# led-ring.net
KiCad netlist of a schematic drawn in EAGLE
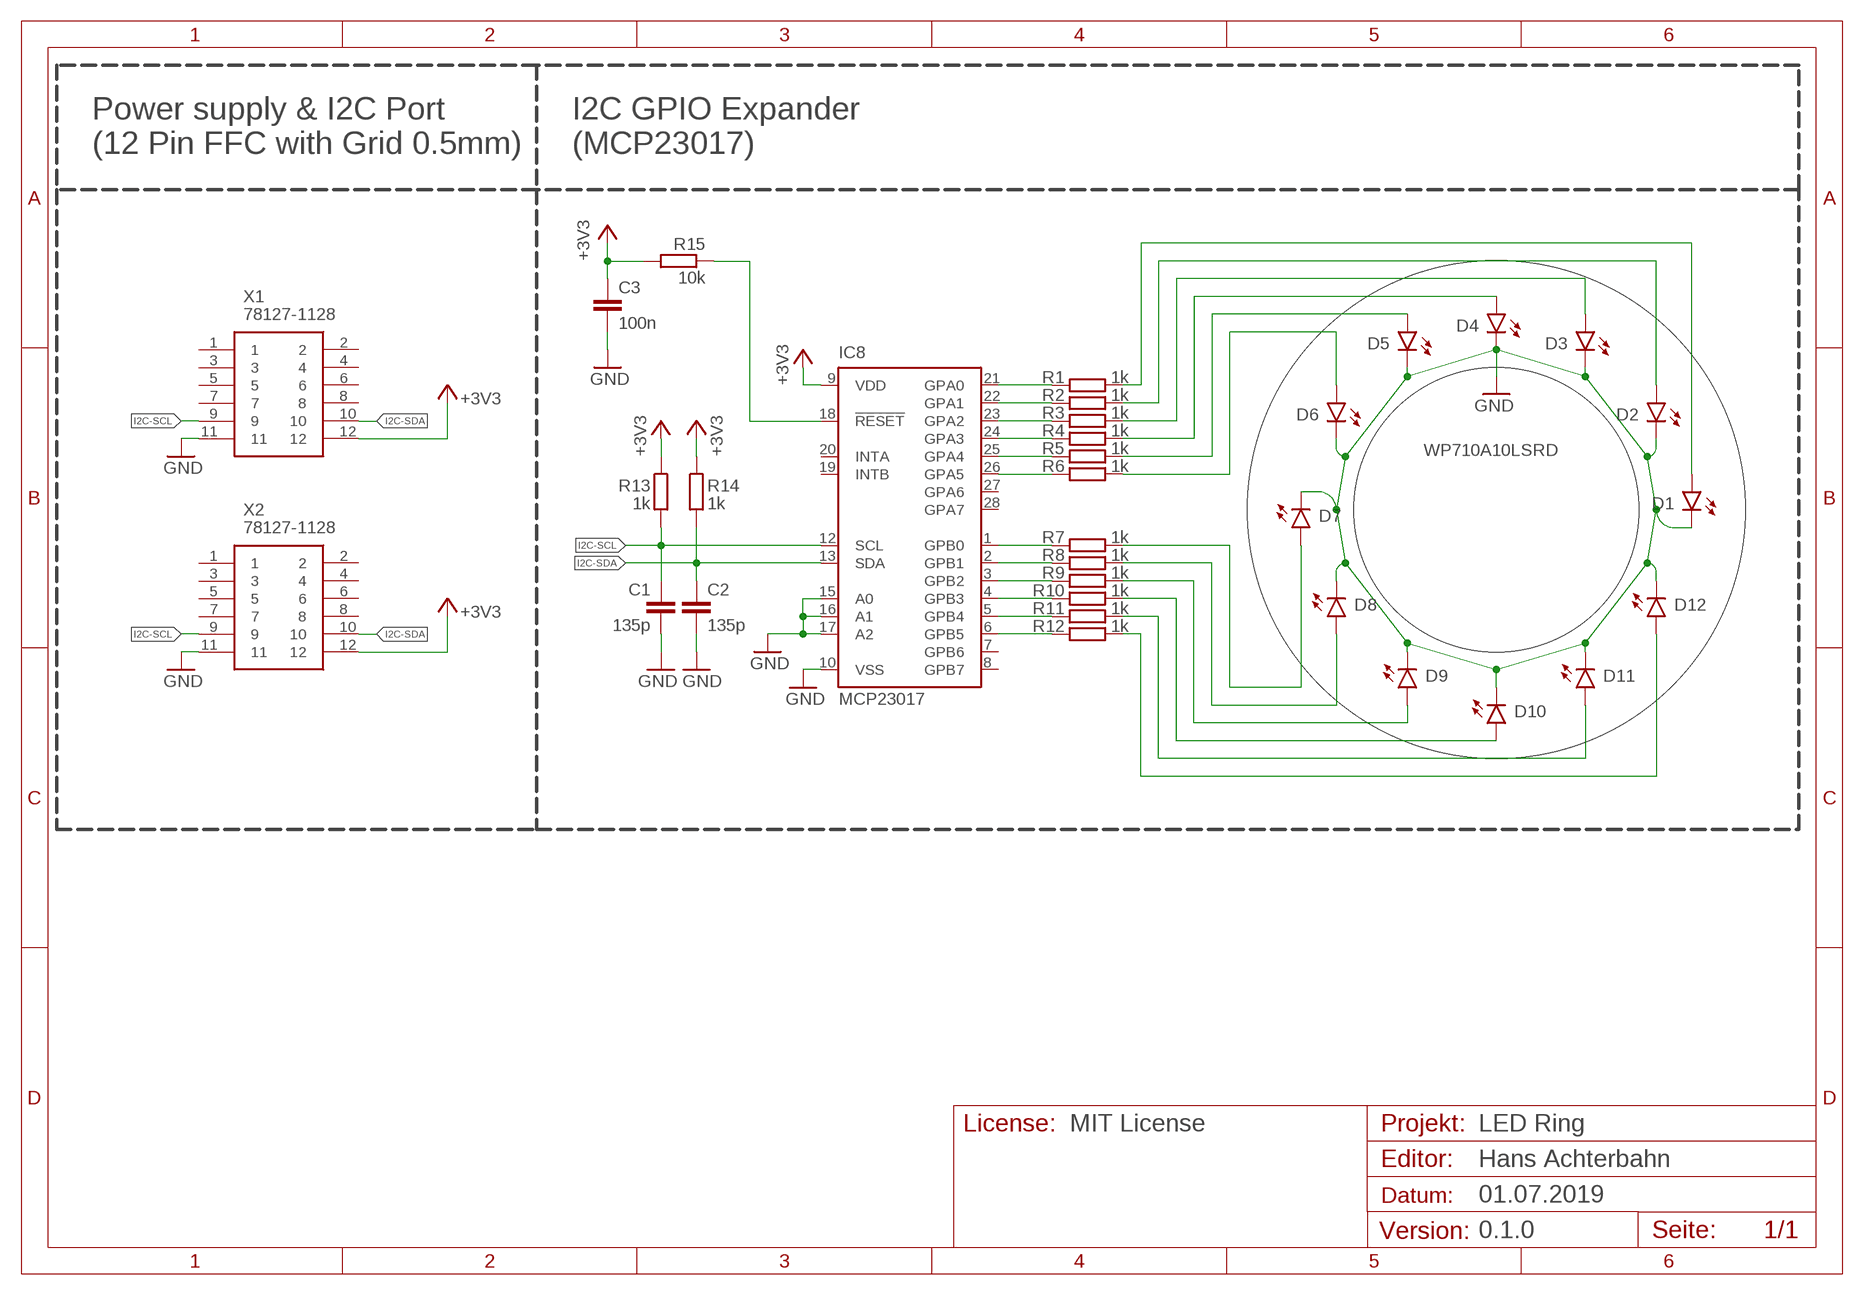
[diagram p0: schematic, sheet 1]

(export (version "E")
  (design (tool "Eeschema 10.0.6"))
  (components
    (comp (ref "C1")
      (value "135p")
      (footprint "eagle-import:C0603")
      (libsource (lib "eagle-import") (part "C-EUC0603"))
    )
    (comp (ref "C2")
      (value "135p")
      (footprint "eagle-import:C0603")
      (libsource (lib "eagle-import") (part "C-EUC0603"))
    )
    (comp (ref "C3")
      (value "100n")
      (footprint "eagle-import:C0603")
      (fields
        (field (name "MF") "AVX")
        (field (name "MFN") "0603YC104JAT2A")
        (field (name "MOUSER") "581-0603YC104J")
        (field (name "RS-ONLINE") "391-246 ")
      )
      (libsource (lib "eagle-import") (part "C-EUC0603"))
    )
    (comp (ref "D1")
      (value "WP710A10LSRD")
      (footprint "eagle-import:RADIAL_3MM")
      (fields
        (field (name "DIGIKEY_PART_NUMBER") "160-1708-ND")
        (field (name "MANUFACTURER") "Lite-On Inc.")
        (field (name "MPN") "LTL-1CHE")
        (field (name "CREATED_BY") "PCBLayout.com")
      )
      (libsource (lib "eagle-import") (part "LTL-1CHE"))
    )
    (comp (ref "D2")
      (value "WP710A10LSRD")
      (footprint "eagle-import:RADIAL_3MM")
      (fields
        (field (name "DIGIKEY_PART_NUMBER") "160-1708-ND")
        (field (name "MANUFACTURER") "Lite-On Inc.")
        (field (name "MPN") "LTL-1CHE")
        (field (name "CREATED_BY") "PCBLayout.com")
      )
      (libsource (lib "eagle-import") (part "LTL-1CHE"))
    )
    (comp (ref "D3")
      (value "WP710A10LSRD")
      (footprint "eagle-import:RADIAL_3MM")
      (fields
        (field (name "DIGIKEY_PART_NUMBER") "160-1708-ND")
        (field (name "MANUFACTURER") "Lite-On Inc.")
        (field (name "MPN") "LTL-1CHE")
        (field (name "CREATED_BY") "PCBLayout.com")
      )
      (libsource (lib "eagle-import") (part "LTL-1CHE"))
    )
    (comp (ref "D4")
      (value "WP710A10LSRD")
      (footprint "eagle-import:RADIAL_3MM")
      (fields
        (field (name "DIGIKEY_PART_NUMBER") "160-1708-ND")
        (field (name "MANUFACTURER") "Lite-On Inc.")
        (field (name "MPN") "LTL-1CHE")
        (field (name "CREATED_BY") "PCBLayout.com")
      )
      (libsource (lib "eagle-import") (part "LTL-1CHE"))
    )
    (comp (ref "D5")
      (value "WP710A10LSRD")
      (footprint "eagle-import:RADIAL_3MM")
      (fields
        (field (name "DIGIKEY_PART_NUMBER") "160-1708-ND")
        (field (name "MANUFACTURER") "Lite-On Inc.")
        (field (name "MPN") "LTL-1CHE")
        (field (name "CREATED_BY") "PCBLayout.com")
      )
      (libsource (lib "eagle-import") (part "LTL-1CHE"))
    )
    (comp (ref "D6")
      (value "WP710A10LSRD")
      (footprint "eagle-import:RADIAL_3MM")
      (fields
        (field (name "DIGIKEY_PART_NUMBER") "160-1708-ND")
        (field (name "MANUFACTURER") "Lite-On Inc.")
        (field (name "MPN") "LTL-1CHE")
        (field (name "CREATED_BY") "PCBLayout.com")
      )
      (libsource (lib "eagle-import") (part "LTL-1CHE"))
    )
    (comp (ref "D7")
      (value "WP710A10LSRD")
      (footprint "eagle-import:RADIAL_3MM")
      (fields
        (field (name "DIGIKEY_PART_NUMBER") "160-1708-ND")
        (field (name "MANUFACTURER") "Lite-On Inc.")
        (field (name "MPN") "LTL-1CHE")
        (field (name "CREATED_BY") "PCBLayout.com")
      )
      (libsource (lib "eagle-import") (part "LTL-1CHE"))
    )
    (comp (ref "D8")
      (value "WP710A10LSRD")
      (footprint "eagle-import:RADIAL_3MM")
      (fields
        (field (name "DIGIKEY_PART_NUMBER") "160-1708-ND")
        (field (name "MANUFACTURER") "Lite-On Inc.")
        (field (name "MPN") "LTL-1CHE")
        (field (name "CREATED_BY") "PCBLayout.com")
      )
      (libsource (lib "eagle-import") (part "LTL-1CHE"))
    )
    (comp (ref "D9")
      (value "WP710A10LSRD")
      (footprint "eagle-import:RADIAL_3MM")
      (fields
        (field (name "DIGIKEY_PART_NUMBER") "160-1708-ND")
        (field (name "MANUFACTURER") "Lite-On Inc.")
        (field (name "MPN") "LTL-1CHE")
        (field (name "CREATED_BY") "PCBLayout.com")
      )
      (libsource (lib "eagle-import") (part "LTL-1CHE"))
    )
    (comp (ref "D10")
      (value "WP710A10LSRD")
      (footprint "eagle-import:RADIAL_3MM")
      (fields
        (field (name "DIGIKEY_PART_NUMBER") "160-1708-ND")
        (field (name "MANUFACTURER") "Lite-On Inc.")
        (field (name "MPN") "LTL-1CHE")
        (field (name "CREATED_BY") "PCBLayout.com")
      )
      (libsource (lib "eagle-import") (part "LTL-1CHE"))
    )
    (comp (ref "D11")
      (value "WP710A10LSRD")
      (footprint "eagle-import:RADIAL_3MM")
      (fields
        (field (name "DIGIKEY_PART_NUMBER") "160-1708-ND")
        (field (name "MANUFACTURER") "Lite-On Inc.")
        (field (name "MPN") "LTL-1CHE")
        (field (name "CREATED_BY") "PCBLayout.com")
      )
      (libsource (lib "eagle-import") (part "LTL-1CHE"))
    )
    (comp (ref "D12")
      (value "WP710A10LSRD")
      (footprint "eagle-import:RADIAL_3MM")
      (fields
        (field (name "DIGIKEY_PART_NUMBER") "160-1708-ND")
        (field (name "MANUFACTURER") "Lite-On Inc.")
        (field (name "MPN") "LTL-1CHE")
        (field (name "CREATED_BY") "PCBLayout.com")
      )
      (libsource (lib "eagle-import") (part "LTL-1CHE"))
    )
    (comp (ref "IC8")
      (value "MCP23017")
      (footprint "eagle-import:SOP65P780X200-28")
      (fields (field (name "MF") "Microchip"))
      (libsource (lib "eagle-import") (part "MCP23017"))
    )
    (comp (ref "R1")
      (value "1k")
      (footprint "eagle-import:R0603")
      (libsource (lib "eagle-import") (part "R-EU_R0603"))
    )
    (comp (ref "R2")
      (value "1k")
      (footprint "eagle-import:R0603")
      (libsource (lib "eagle-import") (part "R-EU_R0603"))
    )
    (comp (ref "R3")
      (value "1k")
      (footprint "eagle-import:R0603")
      (libsource (lib "eagle-import") (part "R-EU_R0603"))
    )
    (comp (ref "R4")
      (value "1k")
      (footprint "eagle-import:R0603")
      (libsource (lib "eagle-import") (part "R-EU_R0603"))
    )
    (comp (ref "R5")
      (value "1k")
      (footprint "eagle-import:R0603")
      (libsource (lib "eagle-import") (part "R-EU_R0603"))
    )
    (comp (ref "R6")
      (value "1k")
      (footprint "eagle-import:R0603")
      (libsource (lib "eagle-import") (part "R-EU_R0603"))
    )
    (comp (ref "R7")
      (value "1k")
      (footprint "eagle-import:R0603")
      (libsource (lib "eagle-import") (part "R-EU_R0603"))
    )
    (comp (ref "R8")
      (value "1k")
      (footprint "eagle-import:R0603")
      (libsource (lib "eagle-import") (part "R-EU_R0603"))
    )
    (comp (ref "R9")
      (value "1k")
      (footprint "eagle-import:R0603")
      (libsource (lib "eagle-import") (part "R-EU_R0603"))
    )
    (comp (ref "R10")
      (value "1k")
      (footprint "eagle-import:R0603")
      (libsource (lib "eagle-import") (part "R-EU_R0603"))
    )
    (comp (ref "R11")
      (value "1k")
      (footprint "eagle-import:R0603")
      (libsource (lib "eagle-import") (part "R-EU_R0603"))
    )
    (comp (ref "R12")
      (value "1k")
      (footprint "eagle-import:R0603")
      (libsource (lib "eagle-import") (part "R-EU_R0603"))
    )
    (comp (ref "R13")
      (value "1k")
      (footprint "eagle-import:R0603")
      (libsource (lib "eagle-import") (part "R-EU_R0603"))
    )
    (comp (ref "R14")
      (value "1k")
      (footprint "eagle-import:R0603")
      (libsource (lib "eagle-import") (part "R-EU_R0603"))
    )
    (comp (ref "R15")
      (value "10k")
      (footprint "eagle-import:R0603")
      (fields (field (name "MF") "Vishay") (field (name "MFN") "CRCW060310K0FKEA"))
      (libsource (lib "eagle-import") (part "R-EU_R0603"))
    )
    (comp (ref "X1")
      (value "78127-1128")
      (footprint "eagle-import:781271128")
      (fields (field (name "MOUSER_PART_NUMBER") "538-78127-1128"))
      (libsource (lib "eagle-import") (part "78127-1128"))
    )
    (comp (ref "X2")
      (value "78127-1128")
      (footprint "eagle-import:781271128")
      (fields (field (name "MOUSER_PART_NUMBER") "538-78127-1128"))
      (libsource (lib "eagle-import") (part "78127-1128"))
    )
  )
  (nets
    (net (code "1") (name "+3V3") (class "Default")
      (node (ref "C3") (pin "1") (pinfunction "1_1") (pintype "passive"))
      (node (ref "IC8") (pin "9") (pinfunction "VDD_9") (pintype "power_in"))
      (node (ref "R13") (pin "1") (pinfunction "1_1") (pintype "passive"))
      (node (ref "R14") (pin "1") (pinfunction "1_1") (pintype "passive"))
      (node (ref "R15") (pin "2") (pinfunction "2_2") (pintype "passive"))
      (node (ref "X1") (pin "12") (pinfunction "12_12") (pintype "bidirectional"))
      (node (ref "X2") (pin "12") (pinfunction "12_12") (pintype "bidirectional"))
    )
    (net (code "2") (name "GND") (class "Default")
      (node (ref "C1") (pin "2") (pinfunction "2_2") (pintype "passive"))
      (node (ref "C2") (pin "2") (pinfunction "2_2") (pintype "passive"))
      (node (ref "C3") (pin "2") (pinfunction "2_2") (pintype "passive"))
      (node (ref "D1") (pin "C") (pinfunction "C_C") (pintype "passive"))
      (node (ref "D10") (pin "C") (pinfunction "C_C") (pintype "passive"))
      (node (ref "D11") (pin "C") (pinfunction "C_C") (pintype "passive"))
      (node (ref "D12") (pin "C") (pinfunction "C_C") (pintype "passive"))
      (node (ref "D2") (pin "C") (pinfunction "C_C") (pintype "passive"))
      (node (ref "D3") (pin "C") (pinfunction "C_C") (pintype "passive"))
      (node (ref "D4") (pin "C") (pinfunction "C_C") (pintype "passive"))
      (node (ref "D5") (pin "C") (pinfunction "C_C") (pintype "passive"))
      (node (ref "D6") (pin "C") (pinfunction "C_C") (pintype "passive"))
      (node (ref "D7") (pin "C") (pinfunction "C_C") (pintype "passive"))
      (node (ref "D8") (pin "C") (pinfunction "C_C") (pintype "passive"))
      (node (ref "D9") (pin "C") (pinfunction "C_C") (pintype "passive"))
      (node (ref "IC8") (pin "10") (pinfunction "VSS_10") (pintype "power_in"))
      (node (ref "IC8") (pin "15") (pinfunction "A0_15") (pintype "input"))
      (node (ref "IC8") (pin "16") (pinfunction "A1_16") (pintype "input"))
      (node (ref "IC8") (pin "17") (pinfunction "A2_17") (pintype "input"))
      (node (ref "X1") (pin "11") (pinfunction "11_11") (pintype "bidirectional"))
      (node (ref "X2") (pin "11") (pinfunction "11_11") (pintype "bidirectional"))
    )
    (net (code "3") (name "I2C-SCL") (class "Default")
      (node (ref "C1") (pin "1") (pinfunction "1_1") (pintype "passive"))
      (node (ref "IC8") (pin "12") (pinfunction "SCL_12") (pintype "input"))
      (node (ref "R13") (pin "2") (pinfunction "2_2") (pintype "passive"))
      (node (ref "X1") (pin "9") (pinfunction "9_9") (pintype "bidirectional"))
      (node (ref "X2") (pin "9") (pinfunction "9_9") (pintype "bidirectional"))
    )
    (net (code "4") (name "I2C-SDA") (class "Default")
      (node (ref "C2") (pin "1") (pinfunction "1_1") (pintype "passive"))
      (node (ref "IC8") (pin "13") (pinfunction "SDA_13") (pintype "bidirectional"))
      (node (ref "R14") (pin "2") (pinfunction "2_2") (pintype "passive"))
      (node (ref "X1") (pin "10") (pinfunction "10_10") (pintype "bidirectional"))
      (node (ref "X2") (pin "10") (pinfunction "10_10") (pintype "bidirectional"))
    )
    (net (code "5") (name "Net-(D1-PadA)") (class "Default")
      (node (ref "D1") (pin "A") (pinfunction "A_A") (pintype "passive"))
      (node (ref "R1") (pin "1") (pinfunction "1_1") (pintype "passive"))
    )
    (net (code "6") (name "Net-(D2-PadA)") (class "Default")
      (node (ref "D2") (pin "A") (pinfunction "A_A") (pintype "passive"))
      (node (ref "R2") (pin "1") (pinfunction "1_1") (pintype "passive"))
    )
    (net (code "7") (name "Net-(D3-PadA)") (class "Default")
      (node (ref "D3") (pin "A") (pinfunction "A_A") (pintype "passive"))
      (node (ref "R3") (pin "1") (pinfunction "1_1") (pintype "passive"))
    )
    (net (code "8") (name "Net-(D4-PadA)") (class "Default")
      (node (ref "D4") (pin "A") (pinfunction "A_A") (pintype "passive"))
      (node (ref "R4") (pin "1") (pinfunction "1_1") (pintype "passive"))
    )
    (net (code "9") (name "Net-(D5-PadA)") (class "Default")
      (node (ref "D5") (pin "A") (pinfunction "A_A") (pintype "passive"))
      (node (ref "R5") (pin "1") (pinfunction "1_1") (pintype "passive"))
    )
    (net (code "10") (name "Net-(D6-PadA)") (class "Default")
      (node (ref "D6") (pin "A") (pinfunction "A_A") (pintype "passive"))
      (node (ref "R6") (pin "1") (pinfunction "1_1") (pintype "passive"))
    )
    (net (code "11") (name "Net-(D7-PadA)") (class "Default")
      (node (ref "D7") (pin "A") (pinfunction "A_A") (pintype "passive"))
      (node (ref "R7") (pin "1") (pinfunction "1_1") (pintype "passive"))
    )
    (net (code "12") (name "Net-(D8-PadA)") (class "Default")
      (node (ref "D8") (pin "A") (pinfunction "A_A") (pintype "passive"))
      (node (ref "R8") (pin "1") (pinfunction "1_1") (pintype "passive"))
    )
    (net (code "13") (name "Net-(D9-PadA)") (class "Default")
      (node (ref "D9") (pin "A") (pinfunction "A_A") (pintype "passive"))
      (node (ref "R9") (pin "1") (pinfunction "1_1") (pintype "passive"))
    )
    (net (code "14") (name "Net-(D10-PadA)") (class "Default")
      (node (ref "D10") (pin "A") (pinfunction "A_A") (pintype "passive"))
      (node (ref "R10") (pin "1") (pinfunction "1_1") (pintype "passive"))
    )
    (net (code "15") (name "Net-(D11-PadA)") (class "Default")
      (node (ref "D11") (pin "A") (pinfunction "A_A") (pintype "passive"))
      (node (ref "R11") (pin "1") (pinfunction "1_1") (pintype "passive"))
    )
    (net (code "16") (name "Net-(D12-PadA)") (class "Default")
      (node (ref "D12") (pin "A") (pinfunction "A_A") (pintype "passive"))
      (node (ref "R12") (pin "1") (pinfunction "1_1") (pintype "passive"))
    )
    (net (code "17") (name "Net-(IC8-GPA0)") (class "Default")
      (node (ref "IC8") (pin "21") (pinfunction "GPA0_21") (pintype "bidirectional"))
      (node (ref "R1") (pin "2") (pinfunction "2_2") (pintype "passive"))
    )
    (net (code "18") (name "Net-(IC8-GPA1)") (class "Default")
      (node (ref "IC8") (pin "22") (pinfunction "GPA1_22") (pintype "bidirectional"))
      (node (ref "R2") (pin "2") (pinfunction "2_2") (pintype "passive"))
    )
    (net (code "19") (name "Net-(IC8-GPA2)") (class "Default")
      (node (ref "IC8") (pin "23") (pinfunction "GPA2_23") (pintype "bidirectional"))
      (node (ref "R3") (pin "2") (pinfunction "2_2") (pintype "passive"))
    )
    (net (code "20") (name "Net-(IC8-GPA3)") (class "Default")
      (node (ref "IC8") (pin "24") (pinfunction "GPA3_24") (pintype "bidirectional"))
      (node (ref "R4") (pin "2") (pinfunction "2_2") (pintype "passive"))
    )
    (net (code "21") (name "Net-(IC8-GPA4)") (class "Default")
      (node (ref "IC8") (pin "25") (pinfunction "GPA4_25") (pintype "bidirectional"))
      (node (ref "R5") (pin "2") (pinfunction "2_2") (pintype "passive"))
    )
    (net (code "22") (name "Net-(IC8-GPA5)") (class "Default")
      (node (ref "IC8") (pin "26") (pinfunction "GPA5_26") (pintype "bidirectional"))
      (node (ref "R6") (pin "2") (pinfunction "2_2") (pintype "passive"))
    )
    (net (code "23") (name "Net-(IC8-GPB0)") (class "Default")
      (node (ref "IC8") (pin "1") (pinfunction "GPB0_1") (pintype "bidirectional"))
      (node (ref "R7") (pin "2") (pinfunction "2_2") (pintype "passive"))
    )
    (net (code "24") (name "Net-(IC8-GPB1)") (class "Default")
      (node (ref "IC8") (pin "2") (pinfunction "GPB1_2") (pintype "bidirectional"))
      (node (ref "R8") (pin "2") (pinfunction "2_2") (pintype "passive"))
    )
    (net (code "25") (name "Net-(IC8-GPB2)") (class "Default")
      (node (ref "IC8") (pin "3") (pinfunction "GPB2_3") (pintype "bidirectional"))
      (node (ref "R9") (pin "2") (pinfunction "2_2") (pintype "passive"))
    )
    (net (code "26") (name "Net-(IC8-GPB3)") (class "Default")
      (node (ref "IC8") (pin "4") (pinfunction "GPB3_4") (pintype "bidirectional"))
      (node (ref "R10") (pin "2") (pinfunction "2_2") (pintype "passive"))
    )
    (net (code "27") (name "Net-(IC8-GPB4)") (class "Default")
      (node (ref "IC8") (pin "5") (pinfunction "GPB4_5") (pintype "bidirectional"))
      (node (ref "R11") (pin "2") (pinfunction "2_2") (pintype "passive"))
    )
    (net (code "28") (name "Net-(IC8-GPB5)") (class "Default")
      (node (ref "IC8") (pin "6") (pinfunction "GPB5_6") (pintype "bidirectional"))
      (node (ref "R12") (pin "2") (pinfunction "2_2") (pintype "passive"))
    )
    (net (code "29") (name "Net-(IC8-~{RESET})") (class "Default")
      (node (ref "IC8") (pin "18") (pinfunction "~{RESET}_18") (pintype "input"))
      (node (ref "R15") (pin "1") (pinfunction "1_1") (pintype "passive"))
    )
    (net (code "30") (name "unconnected-(IC8-GPA6-Pad27)") (class "Default")
      (node (ref "IC8") (pin "27") (pinfunction "GPA6_27") (pintype "bidirectional"))
    )
    (net (code "31") (name "unconnected-(IC8-GPA7-Pad28)") (class "Default")
      (node (ref "IC8") (pin "28") (pinfunction "GPA7_28") (pintype "bidirectional"))
    )
    (net (code "32") (name "unconnected-(IC8-GPB6-Pad7)") (class "Default")
      (node (ref "IC8") (pin "7") (pinfunction "GPB6_7") (pintype "bidirectional"))
    )
    (net (code "33") (name "unconnected-(IC8-GPB7-Pad8)") (class "Default")
      (node (ref "IC8") (pin "8") (pinfunction "GPB7_8") (pintype "bidirectional"))
    )
    (net (code "34") (name "unconnected-(IC8-INTA-Pad20)") (class "Default")
      (node (ref "IC8") (pin "20") (pinfunction "INTA_20") (pintype "output"))
    )
    (net (code "35") (name "unconnected-(IC8-INTB-Pad19)") (class "Default")
      (node (ref "IC8") (pin "19") (pinfunction "INTB_19") (pintype "output"))
    )
    (net (code "36") (name "unconnected-(X1-Pad1)") (class "Default")
      (node (ref "X1") (pin "1") (pinfunction "1_1") (pintype "bidirectional"))
    )
    (net (code "37") (name "unconnected-(X1-Pad2)") (class "Default")
      (node (ref "X1") (pin "2") (pinfunction "2_2") (pintype "bidirectional"))
    )
    (net (code "38") (name "unconnected-(X1-Pad3)") (class "Default")
      (node (ref "X1") (pin "3") (pinfunction "3_3") (pintype "bidirectional"))
    )
    (net (code "39") (name "unconnected-(X1-Pad4)") (class "Default")
      (node (ref "X1") (pin "4") (pinfunction "4_4") (pintype "bidirectional"))
    )
    (net (code "40") (name "unconnected-(X1-Pad5)") (class "Default")
      (node (ref "X1") (pin "5") (pinfunction "5_5") (pintype "bidirectional"))
    )
    (net (code "41") (name "unconnected-(X1-Pad6)") (class "Default")
      (node (ref "X1") (pin "6") (pinfunction "6_6") (pintype "bidirectional"))
    )
    (net (code "42") (name "unconnected-(X1-Pad7)") (class "Default")
      (node (ref "X1") (pin "7") (pinfunction "7_7") (pintype "bidirectional"))
    )
    (net (code "43") (name "unconnected-(X1-Pad8)") (class "Default")
      (node (ref "X1") (pin "8") (pinfunction "8_8") (pintype "bidirectional"))
    )
    (net (code "44") (name "unconnected-(X2-Pad1)") (class "Default")
      (node (ref "X2") (pin "1") (pinfunction "1_1") (pintype "bidirectional"))
    )
    (net (code "45") (name "unconnected-(X2-Pad2)") (class "Default")
      (node (ref "X2") (pin "2") (pinfunction "2_2") (pintype "bidirectional"))
    )
    (net (code "46") (name "unconnected-(X2-Pad3)") (class "Default")
      (node (ref "X2") (pin "3") (pinfunction "3_3") (pintype "bidirectional"))
    )
    (net (code "47") (name "unconnected-(X2-Pad4)") (class "Default")
      (node (ref "X2") (pin "4") (pinfunction "4_4") (pintype "bidirectional"))
    )
    (net (code "48") (name "unconnected-(X2-Pad5)") (class "Default")
      (node (ref "X2") (pin "5") (pinfunction "5_5") (pintype "bidirectional"))
    )
    (net (code "49") (name "unconnected-(X2-Pad6)") (class "Default")
      (node (ref "X2") (pin "6") (pinfunction "6_6") (pintype "bidirectional"))
    )
    (net (code "50") (name "unconnected-(X2-Pad7)") (class "Default")
      (node (ref "X2") (pin "7") (pinfunction "7_7") (pintype "bidirectional"))
    )
    (net (code "51") (name "unconnected-(X2-Pad8)") (class "Default")
      (node (ref "X2") (pin "8") (pinfunction "8_8") (pintype "bidirectional"))
    )
  )
)
